# single_motor_driver_v6.net
KiCad netlist of a schematic drawn in EAGLE
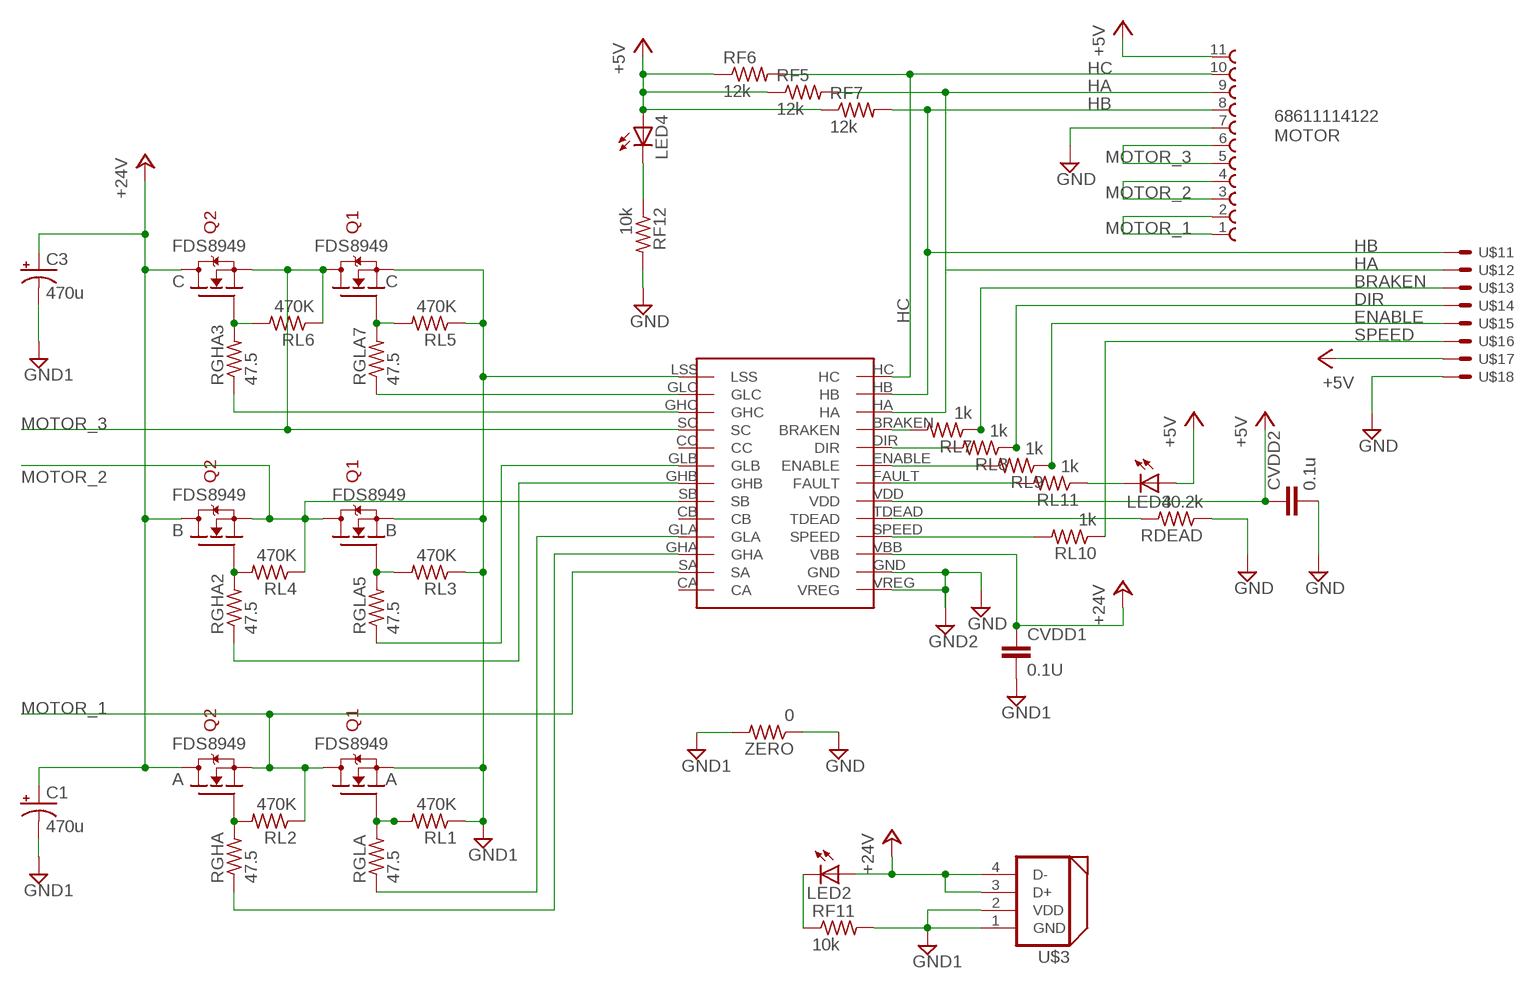
[diagram p0: schematic, sheet 1]

(export (version "E")
  (design (tool "Eeschema 10.0.6"))
  (components
    (comp (ref "A")
      (value "FDS8949")
      (footprint "eagle-import:SOIC8")
      (libsource (lib "eagle-import") (part "FDS8949"))
    )
    (comp (ref "B")
      (value "FDS8949")
      (footprint "eagle-import:SOIC8")
      (libsource (lib "eagle-import") (part "FDS8949"))
    )
    (comp (ref "C")
      (value "FDS8949")
      (footprint "eagle-import:SOIC8")
      (libsource (lib "eagle-import") (part "FDS8949"))
    )
    (comp (ref "C1")
      (value "470u")
      (footprint "eagle-import:140CLH-1010")
      (libsource (lib "eagle-import") (part "CPOL-US140CLH-1010"))
    )
    (comp (ref "C3")
      (value "470u")
      (footprint "eagle-import:140CLH-1010")
      (libsource (lib "eagle-import") (part "CPOL-US140CLH-1010"))
    )
    (comp (ref "CVDD1")
      (value "0.1U")
      (footprint "eagle-import:C0805")
      (libsource (lib "eagle-import") (part "C-EUC0805"))
    )
    (comp (ref "CVDD2")
      (value "0.1u")
      (footprint "eagle-import:C0805")
      (libsource (lib "eagle-import") (part "C-EUC0805"))
    )
    (comp (ref "LED2")
      (value "LEDCHIPLED_0805")
      (footprint "eagle-import:CHIPLED_0805")
      (libsource (lib "eagle-import") (part "LEDCHIPLED_0805"))
    )
    (comp (ref "LED3")
      (value "LEDCHIPLED_0805")
      (footprint "eagle-import:CHIPLED_0805")
      (libsource (lib "eagle-import") (part "LEDCHIPLED_0805"))
    )
    (comp (ref "LED4")
      (value "LEDCHIPLED_0805")
      (footprint "eagle-import:CHIPLED_0805")
      (libsource (lib "eagle-import") (part "LEDCHIPLED_0805"))
    )
    (comp (ref "MOTOR")
      (value "68611114122")
      (footprint "eagle-import:68611114122")
      (libsource (lib "eagle-import") (part "68611114122"))
    )
    (comp (ref "RDEAD")
      (value "40.2k")
      (footprint "eagle-import:R0805")
      (libsource (lib "eagle-import") (part "R-US_R0805"))
    )
    (comp (ref "RF5")
      (value "12k")
      (footprint "eagle-import:R0805")
      (libsource (lib "eagle-import") (part "R-US_R0805"))
    )
    (comp (ref "RF6")
      (value "12k")
      (footprint "eagle-import:R0805")
      (libsource (lib "eagle-import") (part "R-US_R0805"))
    )
    (comp (ref "RF7")
      (value "12k")
      (footprint "eagle-import:R0805")
      (libsource (lib "eagle-import") (part "R-US_R0805"))
    )
    (comp (ref "RF11")
      (value "10k")
      (footprint "eagle-import:R0805")
      (libsource (lib "eagle-import") (part "R-US_R0805"))
    )
    (comp (ref "RF12")
      (value "10k")
      (footprint "eagle-import:R0805")
      (libsource (lib "eagle-import") (part "R-US_R0805"))
    )
    (comp (ref "RGHA")
      (value "47.5")
      (footprint "eagle-import:R0805")
      (libsource (lib "eagle-import") (part "R-US_R0805"))
    )
    (comp (ref "RGHA2")
      (value "47.5")
      (footprint "eagle-import:R0805")
      (libsource (lib "eagle-import") (part "R-US_R0805"))
    )
    (comp (ref "RGHA3")
      (value "47.5")
      (footprint "eagle-import:R0805")
      (libsource (lib "eagle-import") (part "R-US_R0805"))
    )
    (comp (ref "RGLA")
      (value "47.5")
      (footprint "eagle-import:R0805")
      (libsource (lib "eagle-import") (part "R-US_R0805"))
    )
    (comp (ref "RGLA5")
      (value "47.5")
      (footprint "eagle-import:R0805")
      (libsource (lib "eagle-import") (part "R-US_R0805"))
    )
    (comp (ref "RGLA7")
      (value "47.5")
      (footprint "eagle-import:R0805")
      (libsource (lib "eagle-import") (part "R-US_R0805"))
    )
    (comp (ref "RL1")
      (value "470K")
      (footprint "eagle-import:R0805")
      (libsource (lib "eagle-import") (part "R-US_R0805"))
    )
    (comp (ref "RL2")
      (value "470K")
      (footprint "eagle-import:R0805")
      (libsource (lib "eagle-import") (part "R-US_R0805"))
    )
    (comp (ref "RL3")
      (value "470K")
      (footprint "eagle-import:R0805")
      (libsource (lib "eagle-import") (part "R-US_R0805"))
    )
    (comp (ref "RL4")
      (value "470K")
      (footprint "eagle-import:R0805")
      (libsource (lib "eagle-import") (part "R-US_R0805"))
    )
    (comp (ref "RL5")
      (value "470K")
      (footprint "eagle-import:R0805")
      (libsource (lib "eagle-import") (part "R-US_R0805"))
    )
    (comp (ref "RL6")
      (value "470K")
      (footprint "eagle-import:R0805")
      (libsource (lib "eagle-import") (part "R-US_R0805"))
    )
    (comp (ref "RL7")
      (value "1k")
      (footprint "eagle-import:R0805")
      (libsource (lib "eagle-import") (part "R-US_R0805"))
    )
    (comp (ref "RL8")
      (value "1k")
      (footprint "eagle-import:R0805")
      (libsource (lib "eagle-import") (part "R-US_R0805"))
    )
    (comp (ref "RL9")
      (value "1k")
      (footprint "eagle-import:R0805")
      (libsource (lib "eagle-import") (part "R-US_R0805"))
    )
    (comp (ref "RL10")
      (value "1k")
      (footprint "eagle-import:R0805")
      (libsource (lib "eagle-import") (part "R-US_R0805"))
    )
    (comp (ref "RL11")
      (value "1k")
      (footprint "eagle-import:R0805")
      (libsource (lib "eagle-import") (part "R-US_R0805"))
    )
    (comp (ref "U$1")
      (value "JST8")
      (footprint "eagle-import:JST")
      (libsource (lib "eagle-import") (part "JST8"))
    )
    (comp (ref "U$2")
      (value "TSSOP28-BRK")
      (footprint "eagle-import:TSSOP28-BRK")
      (libsource (lib "eagle-import") (part "TSSOP28-BRK"))
    )
    (comp (ref "U$3")
      (value "DYNAMIXEL_RS485")
      (footprint "eagle-import:DYNAMIXEL_SPOX_04")
      (libsource (lib "eagle-import") (part "DYNAMIXEL_RS485"))
    )
    (comp (ref "ZERO")
      (value "0")
      (footprint "eagle-import:R0805")
      (libsource (lib "eagle-import") (part "R-US_R0805"))
    )
  )
  (nets
    (net (code "1") (name "+5V") (class "Default")
      (node (ref "CVDD2") (pin "1") (pinfunction "1_1") (pintype "passive"))
      (node (ref "LED3") (pin "A") (pinfunction "A_A") (pintype "passive"))
      (node (ref "LED4") (pin "A") (pinfunction "A_A") (pintype "passive"))
      (node (ref "MOTOR") (pin "11") (pinfunction "11_11") (pintype "passive"))
      (node (ref "RF5") (pin "1") (pinfunction "1_1") (pintype "passive"))
      (node (ref "RF6") (pin "1") (pinfunction "1_1") (pintype "passive"))
      (node (ref "RF7") (pin "1") (pinfunction "1_1") (pintype "passive"))
      (node (ref "U$1") (pin "7") (pinfunction "S_7") (pintype "passive"))
      (node (ref "U$2") (pin "VDD") (pinfunction "VDD_VDD") (pintype "bidirectional"))
    )
    (net (code "2") (name "+24V") (class "Default")
      (node (ref "A") (pin "5") (pinfunction "D2_5") (pintype "passive"))
      (node (ref "A") (pin "6") (pinfunction "D2_6") (pintype "passive"))
      (node (ref "B") (pin "5") (pinfunction "D2_5") (pintype "passive"))
      (node (ref "B") (pin "6") (pinfunction "D2_6") (pintype "passive"))
      (node (ref "C") (pin "5") (pinfunction "D2_5") (pintype "passive"))
      (node (ref "C") (pin "6") (pinfunction "D2_6") (pintype "passive"))
      (node (ref "C1") (pin "+") (pinfunction "+_+") (pintype "passive"))
      (node (ref "C3") (pin "+") (pinfunction "+_+") (pintype "passive"))
      (node (ref "CVDD1") (pin "1") (pinfunction "1_1") (pintype "passive"))
      (node (ref "LED2") (pin "A") (pinfunction "A_A") (pintype "passive"))
      (node (ref "U$2") (pin "VBB") (pinfunction "VBB_VBB") (pintype "bidirectional"))
      (node (ref "U$3") (pin "3") (pinfunction "D+_3") (pintype "bidirectional"))
      (node (ref "U$3") (pin "4") (pinfunction "D-_4") (pintype "bidirectional"))
    )
    (net (code "3") (name "/BRAKEN") (class "Default")
      (node (ref "RL7") (pin "1") (pinfunction "1_1") (pintype "passive"))
      (node (ref "U$1") (pin "3") (pinfunction "S_3") (pintype "passive"))
    )
    (net (code "4") (name "/DIR") (class "Default")
      (node (ref "RL8") (pin "1") (pinfunction "1_1") (pintype "passive"))
      (node (ref "U$1") (pin "4") (pinfunction "S_4") (pintype "passive"))
    )
    (net (code "5") (name "/ENABLE") (class "Default")
      (node (ref "RL9") (pin "1") (pinfunction "1_1") (pintype "passive"))
      (node (ref "U$1") (pin "5") (pinfunction "S_5") (pintype "passive"))
    )
    (net (code "6") (name "/HA") (class "Default")
      (node (ref "MOTOR") (pin "9") (pinfunction "9_9") (pintype "passive"))
      (node (ref "RF5") (pin "2") (pinfunction "2_2") (pintype "passive"))
      (node (ref "U$1") (pin "2") (pinfunction "S_2") (pintype "passive"))
      (node (ref "U$2") (pin "HA") (pinfunction "HA_HA") (pintype "bidirectional"))
    )
    (net (code "7") (name "/HB") (class "Default")
      (node (ref "MOTOR") (pin "8") (pinfunction "8_8") (pintype "passive"))
      (node (ref "RF7") (pin "2") (pinfunction "2_2") (pintype "passive"))
      (node (ref "U$1") (pin "1") (pinfunction "S_1") (pintype "passive"))
      (node (ref "U$2") (pin "HB") (pinfunction "HB_HB") (pintype "bidirectional"))
    )
    (net (code "8") (name "/HC") (class "Default")
      (node (ref "MOTOR") (pin "10") (pinfunction "10_10") (pintype "passive"))
      (node (ref "RF6") (pin "2") (pinfunction "2_2") (pintype "passive"))
      (node (ref "U$2") (pin "HC") (pinfunction "HC_HC") (pintype "bidirectional"))
    )
    (net (code "9") (name "/MOTOR_1") (class "Default")
      (node (ref "A") (pin "3") (pinfunction "S2_3") (pintype "passive"))
      (node (ref "A") (pin "7") (pinfunction "D1_7") (pintype "passive"))
      (node (ref "A") (pin "8") (pinfunction "D1_8") (pintype "passive"))
      (node (ref "MOTOR") (pin "1") (pinfunction "1_1") (pintype "passive"))
      (node (ref "MOTOR") (pin "2") (pinfunction "2_2") (pintype "passive"))
      (node (ref "RL2") (pin "1") (pinfunction "1_1") (pintype "passive"))
      (node (ref "U$2") (pin "SA") (pinfunction "SA_SA") (pintype "bidirectional"))
    )
    (net (code "10") (name "/MOTOR_2") (class "Default")
      (node (ref "B") (pin "3") (pinfunction "S2_3") (pintype "passive"))
      (node (ref "B") (pin "7") (pinfunction "D1_7") (pintype "passive"))
      (node (ref "B") (pin "8") (pinfunction "D1_8") (pintype "passive"))
      (node (ref "MOTOR") (pin "3") (pinfunction "3_3") (pintype "passive"))
      (node (ref "MOTOR") (pin "4") (pinfunction "4_4") (pintype "passive"))
      (node (ref "RL4") (pin "1") (pinfunction "1_1") (pintype "passive"))
      (node (ref "U$2") (pin "SB") (pinfunction "SB_SB") (pintype "bidirectional"))
    )
    (net (code "11") (name "/MOTOR_3") (class "Default")
      (node (ref "C") (pin "3") (pinfunction "S2_3") (pintype "passive"))
      (node (ref "C") (pin "7") (pinfunction "D1_7") (pintype "passive"))
      (node (ref "C") (pin "8") (pinfunction "D1_8") (pintype "passive"))
      (node (ref "MOTOR") (pin "5") (pinfunction "5_5") (pintype "passive"))
      (node (ref "MOTOR") (pin "6") (pinfunction "6_6") (pintype "passive"))
      (node (ref "RL6") (pin "1") (pinfunction "1_1") (pintype "passive"))
      (node (ref "U$2") (pin "SC") (pinfunction "SC_SC") (pintype "bidirectional"))
    )
    (net (code "12") (name "/SPEED") (class "Default")
      (node (ref "RL10") (pin "1") (pinfunction "1_1") (pintype "passive"))
      (node (ref "U$1") (pin "6") (pinfunction "S_6") (pintype "passive"))
    )
    (net (code "13") (name "GND") (class "Default")
      (node (ref "CVDD2") (pin "2") (pinfunction "2_2") (pintype "passive"))
      (node (ref "MOTOR") (pin "7") (pinfunction "7_7") (pintype "passive"))
      (node (ref "RDEAD") (pin "1") (pinfunction "1_1") (pintype "passive"))
      (node (ref "RF12") (pin "2") (pinfunction "2_2") (pintype "passive"))
      (node (ref "U$1") (pin "8") (pinfunction "S_8") (pintype "passive"))
      (node (ref "U$2") (pin "GND") (pinfunction "GND_GND") (pintype "bidirectional"))
      (node (ref "U$2") (pin "VREG") (pinfunction "VREG_VREG") (pintype "bidirectional"))
      (node (ref "ZERO") (pin "1") (pinfunction "1_1") (pintype "passive"))
    )
    (net (code "14") (name "GND1") (class "Default")
      (node (ref "A") (pin "1") (pinfunction "S1_1") (pintype "passive"))
      (node (ref "B") (pin "1") (pinfunction "S1_1") (pintype "passive"))
      (node (ref "C") (pin "1") (pinfunction "S1_1") (pintype "passive"))
      (node (ref "C1") (pin "-") (pinfunction "-_-") (pintype "passive"))
      (node (ref "C3") (pin "-") (pinfunction "-_-") (pintype "passive"))
      (node (ref "CVDD1") (pin "2") (pinfunction "2_2") (pintype "passive"))
      (node (ref "RF11") (pin "2") (pinfunction "2_2") (pintype "passive"))
      (node (ref "RL1") (pin "1") (pinfunction "1_1") (pintype "passive"))
      (node (ref "RL3") (pin "1") (pinfunction "1_1") (pintype "passive"))
      (node (ref "RL5") (pin "1") (pinfunction "1_1") (pintype "passive"))
      (node (ref "U$2") (pin "LSS") (pinfunction "LSS_LSS") (pintype "bidirectional"))
      (node (ref "U$3") (pin "1") (pinfunction "GND_1") (pintype "power_in"))
      (node (ref "U$3") (pin "2") (pinfunction "VDD_2") (pintype "power_in"))
      (node (ref "ZERO") (pin "2") (pinfunction "2_2") (pintype "passive"))
    )
    (net (code "15") (name "Net-(A-G1)") (class "Default")
      (node (ref "A") (pin "2") (pinfunction "G1_2") (pintype "passive"))
      (node (ref "RGLA") (pin "2") (pinfunction "2_2") (pintype "passive"))
      (node (ref "RL1") (pin "2") (pinfunction "2_2") (pintype "passive"))
    )
    (net (code "16") (name "Net-(A-G2)") (class "Default")
      (node (ref "A") (pin "4") (pinfunction "G2_4") (pintype "passive"))
      (node (ref "RGHA") (pin "2") (pinfunction "2_2") (pintype "passive"))
      (node (ref "RL2") (pin "2") (pinfunction "2_2") (pintype "passive"))
    )
    (net (code "17") (name "Net-(B-G1)") (class "Default")
      (node (ref "B") (pin "2") (pinfunction "G1_2") (pintype "passive"))
      (node (ref "RGLA5") (pin "2") (pinfunction "2_2") (pintype "passive"))
      (node (ref "RL3") (pin "2") (pinfunction "2_2") (pintype "passive"))
    )
    (net (code "18") (name "Net-(B-G2)") (class "Default")
      (node (ref "B") (pin "4") (pinfunction "G2_4") (pintype "passive"))
      (node (ref "RGHA2") (pin "2") (pinfunction "2_2") (pintype "passive"))
      (node (ref "RL4") (pin "2") (pinfunction "2_2") (pintype "passive"))
    )
    (net (code "19") (name "Net-(C-G1)") (class "Default")
      (node (ref "C") (pin "2") (pinfunction "G1_2") (pintype "passive"))
      (node (ref "RGLA7") (pin "2") (pinfunction "2_2") (pintype "passive"))
      (node (ref "RL5") (pin "2") (pinfunction "2_2") (pintype "passive"))
    )
    (net (code "20") (name "Net-(C-G2)") (class "Default")
      (node (ref "C") (pin "4") (pinfunction "G2_4") (pintype "passive"))
      (node (ref "RGHA3") (pin "2") (pinfunction "2_2") (pintype "passive"))
      (node (ref "RL6") (pin "2") (pinfunction "2_2") (pintype "passive"))
    )
    (net (code "21") (name "Net-(LED2-PadC)") (class "Default")
      (node (ref "LED2") (pin "C") (pinfunction "C_C") (pintype "passive"))
      (node (ref "RF11") (pin "1") (pinfunction "1_1") (pintype "passive"))
    )
    (net (code "22") (name "Net-(LED3-PadC)") (class "Default")
      (node (ref "LED3") (pin "C") (pinfunction "C_C") (pintype "passive"))
      (node (ref "RL11") (pin "1") (pinfunction "1_1") (pintype "passive"))
    )
    (net (code "23") (name "Net-(LED4-PadC)") (class "Default")
      (node (ref "LED4") (pin "C") (pinfunction "C_C") (pintype "passive"))
      (node (ref "RF12") (pin "1") (pinfunction "1_1") (pintype "passive"))
    )
    (net (code "24") (name "Net-(RDEAD-Pad2)") (class "Default")
      (node (ref "RDEAD") (pin "2") (pinfunction "2_2") (pintype "passive"))
      (node (ref "U$2") (pin "TDEAD") (pinfunction "TDEAD_TDEAD") (pintype "bidirectional"))
    )
    (net (code "25") (name "Net-(RGHA-Pad1)") (class "Default")
      (node (ref "RGHA") (pin "1") (pinfunction "1_1") (pintype "passive"))
      (node (ref "U$2") (pin "GHA") (pinfunction "GHA_GHA") (pintype "bidirectional"))
    )
    (net (code "26") (name "Net-(RGHA2-Pad1)") (class "Default")
      (node (ref "RGHA2") (pin "1") (pinfunction "1_1") (pintype "passive"))
      (node (ref "U$2") (pin "GHB") (pinfunction "GHB_GHB") (pintype "bidirectional"))
    )
    (net (code "27") (name "Net-(RGHA3-Pad1)") (class "Default")
      (node (ref "RGHA3") (pin "1") (pinfunction "1_1") (pintype "passive"))
      (node (ref "U$2") (pin "GHC") (pinfunction "GHC_GHC") (pintype "bidirectional"))
    )
    (net (code "28") (name "Net-(RGLA-Pad1)") (class "Default")
      (node (ref "RGLA") (pin "1") (pinfunction "1_1") (pintype "passive"))
      (node (ref "U$2") (pin "GLA") (pinfunction "GLA_GLA") (pintype "bidirectional"))
    )
    (net (code "29") (name "Net-(RGLA5-Pad1)") (class "Default")
      (node (ref "RGLA5") (pin "1") (pinfunction "1_1") (pintype "passive"))
      (node (ref "U$2") (pin "GLB") (pinfunction "GLB_GLB") (pintype "bidirectional"))
    )
    (net (code "30") (name "Net-(RGLA7-Pad1)") (class "Default")
      (node (ref "RGLA7") (pin "1") (pinfunction "1_1") (pintype "passive"))
      (node (ref "U$2") (pin "GLC") (pinfunction "GLC_GLC") (pintype "bidirectional"))
    )
    (net (code "31") (name "Net-(RL7-Pad2)") (class "Default")
      (node (ref "RL7") (pin "2") (pinfunction "2_2") (pintype "passive"))
      (node (ref "U$2") (pin "BRAKEN") (pinfunction "BRAKEN_BRAKEN") (pintype "bidirectional"))
    )
    (net (code "32") (name "Net-(RL8-Pad2)") (class "Default")
      (node (ref "RL8") (pin "2") (pinfunction "2_2") (pintype "passive"))
      (node (ref "U$2") (pin "DIR") (pinfunction "DIR_DIR") (pintype "bidirectional"))
    )
    (net (code "33") (name "Net-(RL9-Pad2)") (class "Default")
      (node (ref "RL9") (pin "2") (pinfunction "2_2") (pintype "passive"))
      (node (ref "U$2") (pin "ENABLE") (pinfunction "ENABLE_ENABLE") (pintype "bidirectional"))
    )
    (net (code "34") (name "Net-(RL10-Pad2)") (class "Default")
      (node (ref "RL10") (pin "2") (pinfunction "2_2") (pintype "passive"))
      (node (ref "U$2") (pin "SPEED") (pinfunction "SPEED_SPEED") (pintype "bidirectional"))
    )
    (net (code "35") (name "Net-(RL11-Pad2)") (class "Default")
      (node (ref "RL11") (pin "2") (pinfunction "2_2") (pintype "passive"))
      (node (ref "U$2") (pin "FAULT") (pinfunction "FAULT_FAULT") (pintype "bidirectional"))
    )
    (net (code "36") (name "unconnected-(U$2-PadCA)") (class "Default")
      (node (ref "U$2") (pin "CA") (pinfunction "CA_CA") (pintype "bidirectional"))
    )
    (net (code "37") (name "unconnected-(U$2-PadCB)") (class "Default")
      (node (ref "U$2") (pin "CB") (pinfunction "CB_CB") (pintype "bidirectional"))
    )
    (net (code "38") (name "unconnected-(U$2-PadCC)") (class "Default")
      (node (ref "U$2") (pin "CC") (pinfunction "CC_CC") (pintype "bidirectional"))
    )
  )
)
